# Sensors.net
KiCad netlist of a schematic drawn in Altium Designer
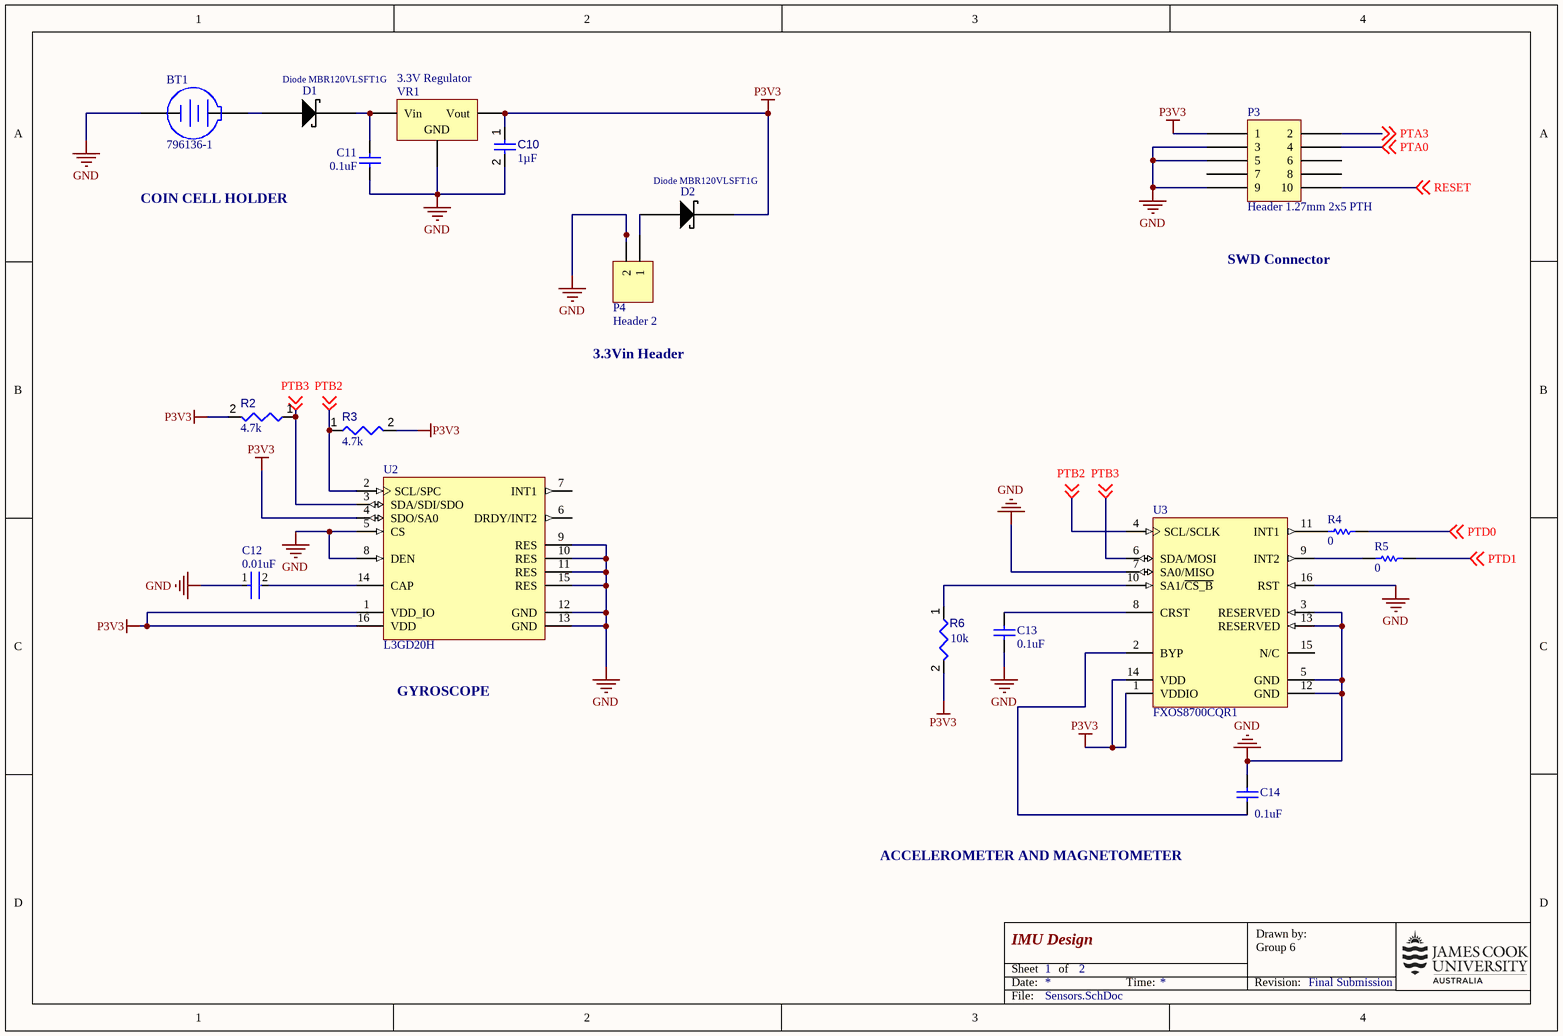
[diagram p0: Sensors.SchDoc]

(export (version "E")
  (design (tool "Eeschema 10.0.6"))
  (components
    (comp (ref "BT1")
      (value "796136-1")
      (footprint "TECO-796136-1_V")
      (description "Battery Connector, 1 Cell, CR2032, 2-Pin SMD, RoHS, Tape and Reel")
      (fields (field (name "MANUFACTURER") "TE Connectivity"))
      (libsource (lib "James Cook University") (part "BATTERY-HOLDER-COIN-2"))
    )
    (comp (ref "C10")
      (value "1µF")
      (footprint "CAPC3216X180X20ML20")
      (description "Chip Capacitor, 1 uF, +/- 10%, 25 V, 1206 (3216 Metric)")
      (fields (field (name "TOLERANCE") "10%") (field (name "Comment") "Capacitor 1 uF +/- 10% 25 V 1206"))
      (libsource (lib "James Cook University") (part "CAP-NP-2"))
    )
    (comp (ref "C11")
      (value "0.1uF")
      (footprint "CAPC3216X95X55NL15T25")
      (description "Chip Capacitor, 0.1 uF, +/- 10%, 50 V, -55 to 125 degC, 1206 (3216 Metric), RoHS, Tape and Reel")
      (fields (field (name "MANUFACTURER") "Murata"))
      (libsource (lib "Altium Content Vault") (part "CAP-NP-2"))
    )
    (comp (ref "C12")
      (value "0.01uF")
      (footprint "FP-C1206C-EB-MFG")
      (description "CAP CER 10000PF 200V X7R 1206")
      (fields
        (field (name "OCTOPART") "https://octopart.com/c1206c103k2ractu-kemet-2299149")
        (field (name "MANUFACTURER") "KEMET")
      )
      (libsource (lib "Altium Content Vault") (part "b4654b650e69147ec39a6b967a45e02"))
    )
    (comp (ref "C13")
      (value "0.1uF")
      (footprint "CAPC3216X95X55NL15T25")
      (description "Chip Capacitor, 0.1 uF, +/- 10%, 50 V, -55 to 125 degC, 1206 (3216 Metric), RoHS, Tape and Reel")
      (fields (field (name "MANUFACTURER") "Murata"))
      (libsource (lib "Altium Content Vault") (part "CAP-NP-2"))
    )
    (comp (ref "C14")
      (value "0.1uF")
      (footprint "CAPC3216X95X55NL15T25")
      (description "Chip Capacitor, 0.1 uF, +/- 10%, 50 V, -55 to 125 degC, 1206 (3216 Metric), RoHS, Tape and Reel")
      (fields (field (name "MANUFACTURER") "Murata"))
      (libsource (lib "Altium Content Vault") (part "CAP-NP-2"))
    )
    (comp (ref "D1")
      (value "Diode MBR120VLSFT1G")
      (footprint "SODFL360X100-2N")
      (description "MBR120VLSFT1G Schottky Rectifier, 20V, 1A")
      (fields (field (name "SOURCE") "JCULibrary.SchLib"))
      (libsource (lib "James Cook University") (part "Diode MBR120VLSFT1G"))
    )
    (comp (ref "D2")
      (value "Diode MBR120VLSFT1G")
      (footprint "SODFL360X100-2N")
      (description "MBR120VLSFT1G Schottky Rectifier, 20V, 1A")
      (fields (field (name "SOURCE") "JCULibrary.SchLib"))
      (libsource (lib "James Cook University") (part "Diode MBR120VLSFT1G"))
    )
    (comp (ref "P3")
      (value "Header 1.27mm 2x5 PTH")
      (footprint "Header 1.27mm 2x5 PTH")
      (description "Header 1.27mm pitch, 2x5, PTH through hole")
      (fields (field (name "SOURCE") "JCULibrary.SchLib"))
      (libsource (lib "James Cook University") (part "Header 1.27mm 2x5 PTH"))
    )
    (comp (ref "P4")
      (value "Header 2")
      (footprint "HDR1X2")
      (description "Header, 2-Pin")
      (fields (field (name "PUBLISHER") "Altium Limited"))
      (libsource (lib "Miscellaneous Connectors") (part "Header 2"))
    )
    (comp (ref "R2")
      (value "4.7k")
      (footprint "RESC3116X70X50ML13T20")
      (description "Chip Resistor, 4.7 KOhm, +/- 1%, 0.25 W, -55 to 155 degC, 1206 (3216 Metric)")
      (fields (field (name "TOLERANCE") "1%") (field (name "POWER") "250mW"))
      (libsource (lib "James Cook University") (part "RES-2"))
    )
    (comp (ref "R3")
      (value "4.7k")
      (footprint "RESC3116X70X50ML13T20")
      (description "Chip Resistor, 4.7 KOhm, +/- 1%, 0.25 W, -55 to 155 degC, 1206 (3216 Metric)")
      (fields (field (name "TOLERANCE") "1%") (field (name "POWER") "250mW"))
      (libsource (lib "James Cook University") (part "RES-2"))
    )
    (comp (ref "R4")
      (value "0")
      (footprint "RESC3216X60X45ML15T20")
      (description "Chip Resistor, 0 Ohm, +/- 5%, 0.25 W, -55 to 155 degC, 1206 (3216 Metric)")
      (fields (field (name "POWER") "250mW") (field (name "TOLERANCE") "5%"))
      (libsource (lib "") (part "RES-2_1"))
    )
    (comp (ref "R5")
      (value "0")
      (footprint "RESC3216X60X45ML15T20")
      (description "Chip Resistor, 0 Ohm, +/- 5%, 0.25 W, -55 to 155 degC, 1206 (3216 Metric)")
      (fields (field (name "POWER") "250mW") (field (name "TOLERANCE") "5%"))
      (libsource (lib "") (part "RES-2_1"))
    )
    (comp (ref "R6")
      (value "10k")
      (footprint "RESC3216X60X45ML15T20")
      (description "Chip Resistor, 10 KOhm, +/- 1%, 0.25 W, -55 to 155 degC, 1206 (3216 Metric)")
      (fields (field (name "POWER") "250mW") (field (name "TOLERANCE") "1%"))
      (libsource (lib "James Cook University") (part "RES-2"))
    )
    (comp (ref "U2")
      (value "L3GD20H")
      (footprint "STM-LGA-16")
      (fields (field (name "TOLERANCE") "20ppm"))
      (libsource (lib "Altium Content Vault") (part "STM-L3GD20H-LGA-16_A"))
    )
    (comp (ref "U3")
      (value "FXOS8700CQR1")
      (footprint "FREE-QFN-16-3000X3000DE_V")
      (fields (field (name "MANUFACTURER") "Freescale"))
      (libsource (lib "Altium Content Vault") (part "FREE-FXOS8700CQR1-16"))
    )
    (comp (ref "VR1")
      (value "3.3V Regulator")
      (footprint "D2PAK_N")
      (description "Voltage Regulator")
      (fields (field (name "PUBLISHER") "Altium Limited"))
      (libsource (lib "Miscellaneous Devices") (part "Volt Reg"))
    )
  )
  (nets
    (net (code "1") (name "GND") (class "Default")
      (node (ref "BT1") (pin "2") (pinfunction "-_2") (pintype "passive"))
      (node (ref "C10") (pin "2") (pinfunction "2_2") (pintype "passive"))
      (node (ref "C11") (pin "2") (pinfunction "2_2") (pintype "passive"))
      (node (ref "C12") (pin "1") (pinfunction "1_1") (pintype "passive"))
      (node (ref "C13") (pin "2") (pinfunction "2_2") (pintype "passive"))
      (node (ref "C14") (pin "2") (pinfunction "2_2") (pintype "passive"))
      (node (ref "P3") (pin "3") (pinfunction "3_3") (pintype "passive"))
      (node (ref "P3") (pin "5") (pinfunction "5_5") (pintype "passive"))
      (node (ref "P3") (pin "9") (pinfunction "9_9") (pintype "passive"))
      (node (ref "P4") (pin "2") (pinfunction "2_2") (pintype "passive"))
      (node (ref "U2") (pin "10") (pinfunction "RES_10") (pintype "passive"))
      (node (ref "U2") (pin "11") (pinfunction "RES_11") (pintype "passive"))
      (node (ref "U2") (pin "12") (pinfunction "GND_12") (pintype "power_in"))
      (node (ref "U2") (pin "13") (pinfunction "GND_13") (pintype "power_in"))
      (node (ref "U2") (pin "15") (pinfunction "RES_15") (pintype "passive"))
      (node (ref "U2") (pin "5") (pinfunction "CS_5") (pintype "input"))
      (node (ref "U2") (pin "8") (pinfunction "DEN_8") (pintype "input"))
      (node (ref "U2") (pin "9") (pinfunction "RES_9") (pintype "passive"))
      (node (ref "U3") (pin "12") (pinfunction "GND_12") (pintype "power_in"))
      (node (ref "U3") (pin "13") (pinfunction "RESERVED_13") (pintype "input"))
      (node (ref "U3") (pin "16") (pinfunction "RST_16") (pintype "input"))
      (node (ref "U3") (pin "3") (pinfunction "RESERVED_3") (pintype "input"))
      (node (ref "U3") (pin "5") (pinfunction "GND_5") (pintype "power_in"))
      (node (ref "U3") (pin "7") (pinfunction "SA0/MISO_7") (pintype "bidirectional"))
      (node (ref "VR1") (pin "2") (pinfunction "GND_2") (pintype "passive"))
    )
    (net (code "2") (name "Net-(BT1-+)") (class "Default")
      (node (ref "BT1") (pin "1") (pinfunction "+_1") (pintype "passive"))
      (node (ref "D1") (pin "2") (pintype "passive"))
    )
    (net (code "3") (name "Net-(D2-Pad2)") (class "Default")
      (node (ref "D2") (pin "2") (pintype "passive"))
      (node (ref "P4") (pin "1") (pinfunction "1_1") (pintype "passive"))
    )
    (net (code "4") (name "Net-(U2-CAP)") (class "Default")
      (node (ref "C12") (pin "2") (pinfunction "2_2") (pintype "passive"))
      (node (ref "U2") (pin "14") (pinfunction "CAP_14") (pintype "passive"))
    )
    (net (code "5") (name "Net-(U3-BYP)") (class "Default")
      (node (ref "C14") (pin "1") (pinfunction "1_1") (pintype "passive"))
      (node (ref "U3") (pin "2") (pinfunction "BYP_2") (pintype "passive"))
    )
    (net (code "6") (name "Net-(U3-CRST)") (class "Default")
      (node (ref "C13") (pin "1") (pinfunction "1_1") (pintype "passive"))
      (node (ref "U3") (pin "8") (pinfunction "CRST_8") (pintype "passive"))
    )
    (net (code "7") (name "Net-(U3-INT1)") (class "Default")
      (node (ref "R4") (pin "1") (pinfunction "1_1") (pintype "passive"))
      (node (ref "U3") (pin "11") (pinfunction "INT1_11") (pintype "output"))
    )
    (net (code "8") (name "Net-(U3-INT2)") (class "Default")
      (node (ref "R5") (pin "1") (pinfunction "1_1") (pintype "passive"))
      (node (ref "U3") (pin "9") (pinfunction "INT2_9") (pintype "output"))
    )
    (net (code "9") (name "Net-(U3-SA1{slash}~{CS_B})") (class "Default")
      (node (ref "R6") (pin "1") (pinfunction "1_1") (pintype "passive"))
      (node (ref "U3") (pin "10") (pinfunction "SA1/~{CS_B}_10") (pintype "input"))
    )
    (net (code "10") (name "Net-(VR1-Vin)") (class "Default")
      (node (ref "C11") (pin "1") (pinfunction "1_1") (pintype "passive"))
      (node (ref "D1") (pin "1") (pintype "passive"))
      (node (ref "VR1") (pin "1") (pinfunction "Vin_1") (pintype "passive"))
    )
    (net (code "11") (name "P3V3") (class "Default")
      (node (ref "C10") (pin "1") (pinfunction "1_1") (pintype "passive"))
      (node (ref "D2") (pin "1") (pintype "passive"))
      (node (ref "P3") (pin "1") (pinfunction "1_1") (pintype "passive"))
      (node (ref "R2") (pin "2") (pinfunction "2_2") (pintype "passive"))
      (node (ref "R3") (pin "2") (pinfunction "2_2") (pintype "passive"))
      (node (ref "R6") (pin "2") (pinfunction "2_2") (pintype "passive"))
      (node (ref "U2") (pin "1") (pinfunction "VDD_IO_1") (pintype "power_in"))
      (node (ref "U2") (pin "16") (pinfunction "VDD_16") (pintype "power_in"))
      (node (ref "U2") (pin "4") (pinfunction "SDO/SA0_4") (pintype "bidirectional"))
      (node (ref "U3") (pin "1") (pinfunction "VDDIO_1") (pintype "power_in"))
      (node (ref "U3") (pin "14") (pinfunction "VDD_14") (pintype "power_in"))
      (node (ref "VR1") (pin "3") (pinfunction "Vout_3") (pintype "passive"))
    )
    (net (code "12") (name "PTA0") (class "Default")
      (node (ref "P3") (pin "4") (pinfunction "4_4") (pintype "passive"))
    )
    (net (code "13") (name "PTA3") (class "Default")
      (node (ref "P3") (pin "2") (pinfunction "2_2") (pintype "passive"))
    )
    (net (code "14") (name "PTB2") (class "Default")
      (node (ref "R3") (pin "1") (pinfunction "1_1") (pintype "passive"))
      (node (ref "U2") (pin "2") (pinfunction "SCL/SPC_2") (pintype "input"))
      (node (ref "U3") (pin "4") (pinfunction "SCL/SCLK_4") (pintype "input"))
    )
    (net (code "15") (name "PTB3") (class "Default")
      (node (ref "R2") (pin "1") (pinfunction "1_1") (pintype "passive"))
      (node (ref "U2") (pin "3") (pinfunction "SDA/SDI/SDO_3") (pintype "bidirectional"))
      (node (ref "U3") (pin "6") (pinfunction "SDA/MOSI_6") (pintype "bidirectional"))
    )
    (net (code "16") (name "PTD0") (class "Default")
      (node (ref "R4") (pin "2") (pinfunction "2_2") (pintype "passive"))
    )
    (net (code "17") (name "PTD1") (class "Default")
      (node (ref "R5") (pin "2") (pinfunction "2_2") (pintype "passive"))
    )
    (net (code "18") (name "RESET") (class "Default")
      (node (ref "P3") (pin "10") (pinfunction "10_10") (pintype "passive"))
    )
    (net (code "19") (name "unconnected-(P3-Pad6)") (class "Default")
      (node (ref "P3") (pin "6") (pinfunction "6_6") (pintype "passive"))
    )
    (net (code "20") (name "unconnected-(P3-Pad7)") (class "Default")
      (node (ref "P3") (pin "7") (pinfunction "7_7") (pintype "passive"))
    )
    (net (code "21") (name "unconnected-(P3-Pad8)") (class "Default")
      (node (ref "P3") (pin "8") (pinfunction "8_8") (pintype "passive"))
    )
    (net (code "22") (name "unconnected-(U2-DRDY{slash}INT2-Pad6)") (class "Default")
      (node (ref "U2") (pin "6") (pinfunction "DRDY/INT2_6") (pintype "output"))
    )
    (net (code "23") (name "unconnected-(U2-INT1-Pad7)") (class "Default")
      (node (ref "U2") (pin "7") (pinfunction "INT1_7") (pintype "output"))
    )
    (net (code "24") (name "unconnected-(U3-N{slash}C-Pad15)") (class "Default")
      (node (ref "U3") (pin "15") (pinfunction "N/C_15") (pintype "passive"))
    )
  )
)
